# RemoteR2_0.net
KiCad netlist of a schematic drawn in EAGLE
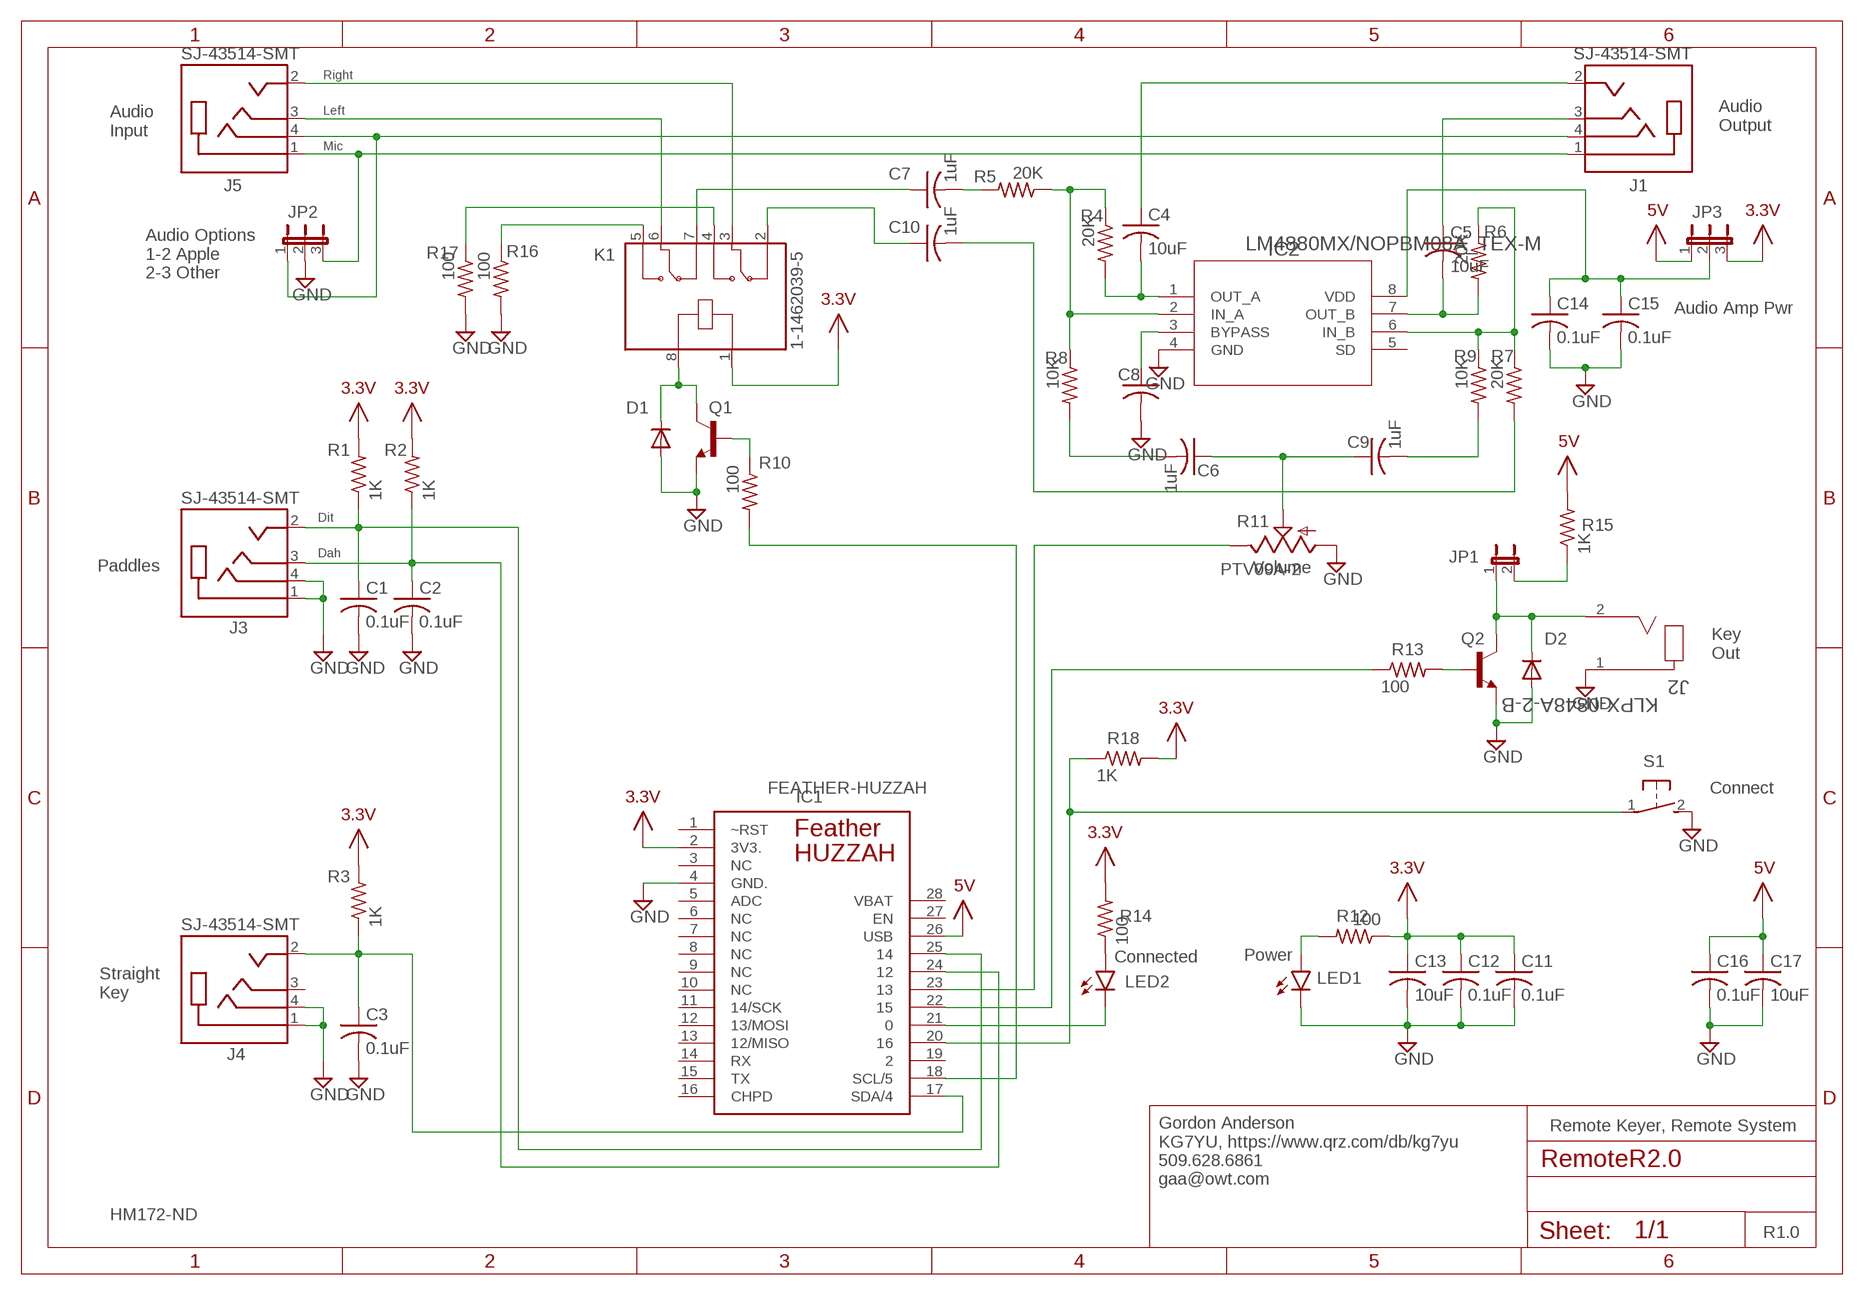
[diagram p0: schematic, sheet 1]

(export (version "E")
  (design (tool "Eeschema 10.0.6"))
  (components
    (comp (ref "C1")
      (value "0.1uF")
      (footprint "eagle-import:C0805")
      (libsource (lib "eagle-import") (part "C-USC0805"))
    )
    (comp (ref "C2")
      (value "0.1uF")
      (footprint "eagle-import:C0805")
      (libsource (lib "eagle-import") (part "C-USC0805"))
    )
    (comp (ref "C3")
      (value "0.1uF")
      (footprint "eagle-import:C0805")
      (libsource (lib "eagle-import") (part "C-USC0805"))
    )
    (comp (ref "C4")
      (value "10uF")
      (footprint "eagle-import:C1206")
      (libsource (lib "eagle-import") (part "C-USC1206"))
    )
    (comp (ref "C5")
      (value "10uF")
      (footprint "eagle-import:C1206")
      (libsource (lib "eagle-import") (part "C-USC1206"))
    )
    (comp (ref "C6")
      (value "1uF")
      (footprint "eagle-import:C0805")
      (libsource (lib "eagle-import") (part "C-USC0805"))
    )
    (comp (ref "C7")
      (value "1uF")
      (footprint "eagle-import:C0805")
      (libsource (lib "eagle-import") (part "C-USC0805"))
    )
    (comp (ref "C8")
      (value "C-USC0805")
      (footprint "eagle-import:C0805")
      (libsource (lib "eagle-import") (part "C-USC0805"))
    )
    (comp (ref "C9")
      (value "1uF")
      (footprint "eagle-import:C0805")
      (libsource (lib "eagle-import") (part "C-USC0805"))
    )
    (comp (ref "C10")
      (value "1uF")
      (footprint "eagle-import:C0805")
      (libsource (lib "eagle-import") (part "C-USC0805"))
    )
    (comp (ref "C11")
      (value "0.1uF")
      (footprint "eagle-import:C0805")
      (libsource (lib "eagle-import") (part "C-USC0805"))
    )
    (comp (ref "C12")
      (value "0.1uF")
      (footprint "eagle-import:C0805")
      (libsource (lib "eagle-import") (part "C-USC0805"))
    )
    (comp (ref "C13")
      (value "10uF")
      (footprint "eagle-import:C0805")
      (libsource (lib "eagle-import") (part "C-USC0805"))
    )
    (comp (ref "C14")
      (value "0.1uF")
      (footprint "eagle-import:C0805")
      (libsource (lib "eagle-import") (part "C-USC0805"))
    )
    (comp (ref "C15")
      (value "0.1uF")
      (footprint "eagle-import:C0805")
      (libsource (lib "eagle-import") (part "C-USC0805"))
    )
    (comp (ref "C16")
      (value "0.1uF")
      (footprint "eagle-import:C0805")
      (libsource (lib "eagle-import") (part "C-USC0805"))
    )
    (comp (ref "C17")
      (value "10uF")
      (footprint "eagle-import:C0805")
      (libsource (lib "eagle-import") (part "C-USC0805"))
    )
    (comp (ref "D1")
      (value "DIODE-SOD323-R")
      (footprint "eagle-import:SOD323-R")
      (libsource (lib "eagle-import") (part "DIODE-SOD323-R"))
    )
    (comp (ref "D2")
      (value "DIODE-SOD323-R")
      (footprint "eagle-import:SOD323-R")
      (libsource (lib "eagle-import") (part "DIODE-SOD323-R"))
    )
    (comp (ref "IC1")
      (value "FEATHER-HUZZAH")
      (footprint "eagle-import:FEATHER-HUZZAH")
      (libsource (lib "eagle-import") (part "FEATHER-HUZZAH"))
    )
    (comp (ref "IC2")
      (value "LM4880MX/NOPBM08A_TEX-M")
      (footprint "eagle-import:M08A_TEX-M")
      (fields
        (field (name "MANUFACTURER_PART_NUMBER") "LM4880MX/NOPB")
        (field (name "COPYRIGHT") "Copyright (C) 2021 Ultra Librarian. All rights reserved.")
      )
      (libsource (lib "eagle-import") (part "LM4880MX/NOPBM08A_TEX-M"))
    )
    (comp (ref "J1")
      (value "SJ-43514-SMT")
      (footprint "eagle-import:CUI_SJ-43514-SMT")
      (fields (field (name "MF") "CUI Devices") (field (name "MP") "SJ-43514-SMT-TR"))
      (libsource (lib "eagle-import") (part "SJ-43514-SMT"))
    )
    (comp (ref "J2")
      (value "KLPX-0848A-2-B")
      (footprint "eagle-import:KLPX-0848A-2-B_KYC")
      (fields (field (name "COPYRIGHT") "Copyright (C) 2021 Ultra Librarian. All rights reserved."))
      (libsource (lib "eagle-import") (part "KLPX-0848A-2-B"))
    )
    (comp (ref "J3")
      (value "SJ-43514-SMT")
      (footprint "eagle-import:CUI_SJ-43514-SMT")
      (fields (field (name "MF") "CUI Devices") (field (name "MP") "SJ-43514-SMT-TR"))
      (libsource (lib "eagle-import") (part "SJ-43514-SMT"))
    )
    (comp (ref "J4")
      (value "SJ-43514-SMT")
      (footprint "eagle-import:CUI_SJ-43514-SMT")
      (fields (field (name "MF") "CUI Devices") (field (name "MP") "SJ-43514-SMT-TR"))
      (libsource (lib "eagle-import") (part "SJ-43514-SMT"))
    )
    (comp (ref "J5")
      (value "SJ-43514-SMT")
      (footprint "eagle-import:CUI_SJ-43514-SMT")
      (fields (field (name "MF") "CUI Devices") (field (name "MP") "SJ-43514-SMT-TR"))
      (libsource (lib "eagle-import") (part "SJ-43514-SMT"))
    )
    (comp (ref "JP1")
      (value "JP1E")
      (footprint "eagle-import:JP1")
      (libsource (lib "eagle-import") (part "JP1E"))
    )
    (comp (ref "JP2")
      (value "JP2E")
      (footprint "eagle-import:JP2")
      (libsource (lib "eagle-import") (part "JP2E"))
    )
    (comp (ref "JP3")
      (value "JP2E")
      (footprint "eagle-import:JP2")
      (libsource (lib "eagle-import") (part "JP2E"))
    )
    (comp (ref "K1")
      (value "1-1462039-5")
      (footprint "eagle-import:RELAY_1-1462039-5")
      (fields (field (name "DIGI-KEY_PART_NUMBER") "PB1167-ND") (field (name "MF") "TE Connectivity"))
      (libsource (lib "eagle-import") (part "1-1462039-5"))
    )
    (comp (ref "LED1")
      (value "LED5MM")
      (footprint "eagle-import:LED5MM")
      (libsource (lib "eagle-import") (part "LED5MM"))
    )
    (comp (ref "LED2")
      (value "LED5MM")
      (footprint "eagle-import:LED5MM")
      (libsource (lib "eagle-import") (part "LED5MM"))
    )
    (comp (ref "Q1")
      (value "MMBT2369LT1-NPN-SOT23-BEC")
      (footprint "eagle-import:SOT23-BEC")
      (libsource (lib "eagle-import") (part "-NPN-SOT23-BECMMBT2369LT1"))
    )
    (comp (ref "Q2")
      (value "MMBT2369LT1-NPN-SOT23-BEC")
      (footprint "eagle-import:SOT23-BEC")
      (libsource (lib "eagle-import") (part "-NPN-SOT23-BECMMBT2369LT1"))
    )
    (comp (ref "R1")
      (value "1K")
      (footprint "eagle-import:R0805")
      (libsource (lib "eagle-import") (part "R-US_R0805"))
    )
    (comp (ref "R2")
      (value "1K")
      (footprint "eagle-import:R0805")
      (libsource (lib "eagle-import") (part "R-US_R0805"))
    )
    (comp (ref "R3")
      (value "1K")
      (footprint "eagle-import:R0805")
      (libsource (lib "eagle-import") (part "R-US_R0805"))
    )
    (comp (ref "R4")
      (value "20K")
      (footprint "eagle-import:R0805")
      (libsource (lib "eagle-import") (part "R-US_R0805"))
    )
    (comp (ref "R5")
      (value "20K")
      (footprint "eagle-import:R0805")
      (libsource (lib "eagle-import") (part "R-US_R0805"))
    )
    (comp (ref "R6")
      (value "20K")
      (footprint "eagle-import:R0805")
      (libsource (lib "eagle-import") (part "R-US_R0805"))
    )
    (comp (ref "R7")
      (value "20K")
      (footprint "eagle-import:R0805")
      (libsource (lib "eagle-import") (part "R-US_R0805"))
    )
    (comp (ref "R8")
      (value "10K")
      (footprint "eagle-import:R0805")
      (libsource (lib "eagle-import") (part "R-US_R0805"))
    )
    (comp (ref "R9")
      (value "10K")
      (footprint "eagle-import:R0805")
      (libsource (lib "eagle-import") (part "R-US_R0805"))
    )
    (comp (ref "R10")
      (value "100")
      (footprint "eagle-import:R0805")
      (libsource (lib "eagle-import") (part "R-US_R0805"))
    )
    (comp (ref "R11")
      (value "PTV09A-2")
      (footprint "eagle-import:PTV09A-2")
      (libsource (lib "eagle-import") (part "PTV09A-2"))
    )
    (comp (ref "R12")
      (value "100")
      (footprint "eagle-import:R0805")
      (libsource (lib "eagle-import") (part "R-US_R0805"))
    )
    (comp (ref "R13")
      (value "100")
      (footprint "eagle-import:R0805")
      (libsource (lib "eagle-import") (part "R-US_R0805"))
    )
    (comp (ref "R14")
      (value "100")
      (footprint "eagle-import:R0805")
      (libsource (lib "eagle-import") (part "R-US_R0805"))
    )
    (comp (ref "R15")
      (value "1K")
      (footprint "eagle-import:R0805")
      (libsource (lib "eagle-import") (part "R-US_R0805"))
    )
    (comp (ref "R16")
      (value "100")
      (footprint "eagle-import:R1206")
      (libsource (lib "eagle-import") (part "R-US_R1206"))
    )
    (comp (ref "R17")
      (value "100")
      (footprint "eagle-import:R1206")
      (libsource (lib "eagle-import") (part "R-US_R1206"))
    )
    (comp (ref "R18")
      (value "1K")
      (footprint "eagle-import:R0805")
      (libsource (lib "eagle-import") (part "R-US_R0805"))
    )
    (comp (ref "S1")
      (value "31-XX")
      (footprint "eagle-import:B3F-31XX")
      (fields (field (name "MPN") "B3F-3100"))
      (libsource (lib "eagle-import") (part "31-XX"))
    )
  )
  (nets
    (net (code "1") (name "/CHPD") (class "Default")
      (node (ref "IC1") (pin "16") (pinfunction "CHPD_16") (pintype "power_in"))
    )
    (net (code "2") (name "/VBAT") (class "Default")
      (node (ref "IC1") (pin "28") (pinfunction "VBAT_28") (pintype "power_in"))
    )
    (net (code "3") (name "3.3V") (class "Default")
      (node (ref "C11") (pin "1") (pinfunction "1_1") (pintype "passive"))
      (node (ref "C12") (pin "1") (pinfunction "1_1") (pintype "passive"))
      (node (ref "C13") (pin "1") (pinfunction "1_1") (pintype "passive"))
      (node (ref "IC1") (pin "2") (pinfunction "3V3._2") (pintype "power_in"))
      (node (ref "JP3") (pin "3") (pinfunction "3_3") (pintype "passive"))
      (node (ref "K1") (pin "1") (pinfunction "1_1") (pintype "passive"))
      (node (ref "R1") (pin "2") (pinfunction "2_2") (pintype "passive"))
      (node (ref "R12") (pin "1") (pinfunction "1_1") (pintype "passive"))
      (node (ref "R14") (pin "2") (pinfunction "2_2") (pintype "passive"))
      (node (ref "R18") (pin "2") (pinfunction "2_2") (pintype "passive"))
      (node (ref "R2") (pin "2") (pinfunction "2_2") (pintype "passive"))
      (node (ref "R3") (pin "2") (pinfunction "2_2") (pintype "passive"))
    )
    (net (code "4") (name "5V") (class "Default")
      (node (ref "C16") (pin "1") (pinfunction "1_1") (pintype "passive"))
      (node (ref "C17") (pin "1") (pinfunction "1_1") (pintype "passive"))
      (node (ref "IC1") (pin "26") (pinfunction "USB_26") (pintype "power_in"))
      (node (ref "JP3") (pin "1") (pinfunction "1_1") (pintype "passive"))
      (node (ref "R15") (pin "2") (pinfunction "2_2") (pintype "passive"))
    )
    (net (code "5") (name "GND") (class "Default")
      (node (ref "C1") (pin "2") (pinfunction "2_2") (pintype "passive"))
      (node (ref "C11") (pin "2") (pinfunction "2_2") (pintype "passive"))
      (node (ref "C12") (pin "2") (pinfunction "2_2") (pintype "passive"))
      (node (ref "C13") (pin "2") (pinfunction "2_2") (pintype "passive"))
      (node (ref "C14") (pin "2") (pinfunction "2_2") (pintype "passive"))
      (node (ref "C15") (pin "2") (pinfunction "2_2") (pintype "passive"))
      (node (ref "C16") (pin "2") (pinfunction "2_2") (pintype "passive"))
      (node (ref "C17") (pin "2") (pinfunction "2_2") (pintype "passive"))
      (node (ref "C2") (pin "2") (pinfunction "2_2") (pintype "passive"))
      (node (ref "C3") (pin "2") (pinfunction "2_2") (pintype "passive"))
      (node (ref "C8") (pin "2") (pinfunction "2_2") (pintype "passive"))
      (node (ref "D1") (pin "A") (pinfunction "A_A") (pintype "passive"))
      (node (ref "D2") (pin "A") (pinfunction "A_A") (pintype "passive"))
      (node (ref "IC1") (pin "4") (pinfunction "GND._4") (pintype "power_in"))
      (node (ref "IC2") (pin "4") (pinfunction "GND_4") (pintype "power_in"))
      (node (ref "J2") (pin "1") (pinfunction "1_1") (pintype "passive"))
      (node (ref "J3") (pin "1") (pinfunction "SLEEVE_1") (pintype "passive"))
      (node (ref "J3") (pin "4") (pinfunction "RING2_4") (pintype "passive"))
      (node (ref "J4") (pin "1") (pinfunction "SLEEVE_1") (pintype "passive"))
      (node (ref "J4") (pin "4") (pinfunction "RING2_4") (pintype "passive"))
      (node (ref "JP2") (pin "2") (pinfunction "2_2") (pintype "passive"))
      (node (ref "LED1") (pin "K") (pinfunction "C_K") (pintype "passive"))
      (node (ref "Q1") (pin "E") (pinfunction "E_E") (pintype "passive"))
      (node (ref "Q2") (pin "E") (pinfunction "E_E") (pintype "passive"))
      (node (ref "R11") (pin "1") (pinfunction "A_1") (pintype "passive"))
      (node (ref "R16") (pin "2") (pinfunction "2_2") (pintype "passive"))
      (node (ref "R17") (pin "2") (pinfunction "2_2") (pintype "passive"))
      (node (ref "S1") (pin "2") (pinfunction "S_2") (pintype "passive"))
    )
    (net (code "6") (name "Net-(C6-Pad2)") (class "Default")
      (node (ref "C6") (pin "2") (pinfunction "2_2") (pintype "passive"))
      (node (ref "R8") (pin "2") (pinfunction "2_2") (pintype "passive"))
    )
    (net (code "7") (name "Net-(C7-Pad1)") (class "Default")
      (node (ref "C7") (pin "1") (pinfunction "1_1") (pintype "passive"))
      (node (ref "K1") (pin "7") (pinfunction "7_7") (pintype "passive"))
    )
    (net (code "8") (name "Net-(C7-Pad2)") (class "Default")
      (node (ref "C7") (pin "2") (pinfunction "2_2") (pintype "passive"))
      (node (ref "R5") (pin "2") (pinfunction "2_2") (pintype "passive"))
    )
    (net (code "9") (name "Net-(C9-Pad2)") (class "Default")
      (node (ref "C9") (pin "2") (pinfunction "2_2") (pintype "passive"))
      (node (ref "R9") (pin "2") (pinfunction "2_2") (pintype "passive"))
    )
    (net (code "10") (name "Net-(C10-Pad1)") (class "Default")
      (node (ref "C10") (pin "1") (pinfunction "1_1") (pintype "passive"))
      (node (ref "K1") (pin "2") (pinfunction "2_2") (pintype "passive"))
    )
    (net (code "11") (name "Net-(C10-Pad2)") (class "Default")
      (node (ref "C10") (pin "2") (pinfunction "2_2") (pintype "passive"))
      (node (ref "R7") (pin "2") (pinfunction "2_2") (pintype "passive"))
    )
    (net (code "12") (name "Net-(D1-PadC)") (class "Default")
      (node (ref "D1") (pin "C") (pinfunction "C_C") (pintype "passive"))
      (node (ref "K1") (pin "8") (pinfunction "8_8") (pintype "passive"))
      (node (ref "Q1") (pin "C") (pinfunction "C_C") (pintype "passive"))
    )
    (net (code "13") (name "Net-(D2-PadC)") (class "Default")
      (node (ref "D2") (pin "C") (pinfunction "C_C") (pintype "passive"))
      (node (ref "J2") (pin "2") (pinfunction "2_2") (pintype "passive"))
      (node (ref "JP1") (pin "1") (pinfunction "1_1") (pintype "passive"))
      (node (ref "Q2") (pin "C") (pinfunction "C_C") (pintype "passive"))
    )
    (net (code "14") (name "Net-(IC1-0)") (class "Default")
      (node (ref "IC1") (pin "21") (pinfunction "0_21") (pintype "bidirectional"))
      (node (ref "LED2") (pin "K") (pinfunction "C_K") (pintype "passive"))
    )
    (net (code "15") (name "Net-(IC1-12)") (class "Default")
      (node (ref "C2") (pin "1") (pinfunction "1_1") (pintype "passive"))
      (node (ref "IC1") (pin "24") (pinfunction "12_24") (pintype "bidirectional"))
      (node (ref "J3") (pin "3") (pinfunction "RING1_3") (pintype "passive"))
      (node (ref "R2") (pin "1") (pinfunction "1_1") (pintype "passive"))
    )
    (net (code "16") (name "Net-(IC1-13)") (class "Default")
      (node (ref "IC1") (pin "23") (pinfunction "13_23") (pintype "bidirectional"))
      (node (ref "R11") (pin "3") (pinfunction "E_3") (pintype "passive"))
    )
    (net (code "17") (name "Net-(IC1-14)") (class "Default")
      (node (ref "C1") (pin "1") (pinfunction "1_1") (pintype "passive"))
      (node (ref "IC1") (pin "25") (pinfunction "14_25") (pintype "bidirectional"))
      (node (ref "J3") (pin "2") (pinfunction "TIP_2") (pintype "passive"))
      (node (ref "R1") (pin "1") (pinfunction "1_1") (pintype "passive"))
    )
    (net (code "18") (name "Net-(IC1-15)") (class "Default")
      (node (ref "IC1") (pin "22") (pinfunction "15_22") (pintype "bidirectional"))
      (node (ref "R13") (pin "1") (pinfunction "1_1") (pintype "passive"))
    )
    (net (code "19") (name "Net-(IC1-16)") (class "Default")
      (node (ref "IC1") (pin "20") (pinfunction "16_20") (pintype "bidirectional"))
      (node (ref "R18") (pin "1") (pinfunction "1_1") (pintype "passive"))
      (node (ref "S1") (pin "1") (pinfunction "P_1") (pintype "passive"))
    )
    (net (code "20") (name "Net-(IC1-SCL{slash}5)") (class "Default")
      (node (ref "IC1") (pin "18") (pinfunction "SCL/5_18") (pintype "bidirectional"))
      (node (ref "R10") (pin "2") (pinfunction "2_2") (pintype "passive"))
    )
    (net (code "21") (name "Net-(IC1-SDA{slash}4)") (class "Default")
      (node (ref "C3") (pin "1") (pinfunction "1_1") (pintype "passive"))
      (node (ref "IC1") (pin "17") (pinfunction "SDA/4_17") (pintype "bidirectional"))
      (node (ref "J4") (pin "2") (pinfunction "TIP_2") (pintype "passive"))
      (node (ref "R3") (pin "1") (pinfunction "1_1") (pintype "passive"))
    )
    (net (code "22") (name "Net-(IC2-BYPASS)") (class "Default")
      (node (ref "C8") (pin "1") (pinfunction "1_1") (pintype "passive"))
      (node (ref "IC2") (pin "3") (pinfunction "BYPASS_3") (pintype "passive"))
    )
    (net (code "23") (name "Net-(IC2-IN_A)") (class "Default")
      (node (ref "IC2") (pin "2") (pinfunction "IN_A_2") (pintype "input"))
      (node (ref "R4") (pin "1") (pinfunction "1_1") (pintype "passive"))
      (node (ref "R5") (pin "1") (pinfunction "1_1") (pintype "passive"))
      (node (ref "R8") (pin "1") (pinfunction "1_1") (pintype "passive"))
    )
    (net (code "24") (name "Net-(IC2-IN_B)") (class "Default")
      (node (ref "IC2") (pin "6") (pinfunction "IN_B_6") (pintype "input"))
      (node (ref "R6") (pin "1") (pinfunction "1_1") (pintype "passive"))
      (node (ref "R7") (pin "1") (pinfunction "1_1") (pintype "passive"))
      (node (ref "R9") (pin "1") (pinfunction "1_1") (pintype "passive"))
    )
    (net (code "25") (name "Net-(IC2-OUT_A)") (class "Default")
      (node (ref "C4") (pin "2") (pinfunction "2_2") (pintype "passive"))
      (node (ref "IC2") (pin "1") (pinfunction "OUT_A_1") (pintype "output"))
      (node (ref "R4") (pin "2") (pinfunction "2_2") (pintype "passive"))
    )
    (net (code "26") (name "Net-(IC2-OUT_B)") (class "Default")
      (node (ref "C5") (pin "2") (pinfunction "2_2") (pintype "passive"))
      (node (ref "IC2") (pin "7") (pinfunction "OUT_B_7") (pintype "output"))
      (node (ref "R6") (pin "2") (pinfunction "2_2") (pintype "passive"))
    )
    (net (code "27") (name "Net-(IC2-VDD)") (class "Default")
      (node (ref "C14") (pin "1") (pinfunction "1_1") (pintype "passive"))
      (node (ref "C15") (pin "1") (pinfunction "1_1") (pintype "passive"))
      (node (ref "IC2") (pin "8") (pinfunction "VDD_8") (pintype "power_in"))
      (node (ref "JP3") (pin "2") (pinfunction "2_2") (pintype "passive"))
    )
    (net (code "28") (name "Net-(J1-RING1)") (class "Default")
      (node (ref "C5") (pin "1") (pinfunction "1_1") (pintype "passive"))
      (node (ref "J1") (pin "3") (pinfunction "RING1_3") (pintype "passive"))
    )
    (net (code "29") (name "Net-(J1-RING2)") (class "Default")
      (node (ref "J1") (pin "4") (pinfunction "RING2_4") (pintype "passive"))
      (node (ref "J5") (pin "4") (pinfunction "RING2_4") (pintype "passive"))
      (node (ref "JP2") (pin "1") (pinfunction "1_1") (pintype "passive"))
    )
    (net (code "30") (name "Net-(J1-SLEEVE)") (class "Default")
      (node (ref "J1") (pin "1") (pinfunction "SLEEVE_1") (pintype "passive"))
      (node (ref "J5") (pin "1") (pinfunction "SLEEVE_1") (pintype "passive"))
      (node (ref "JP2") (pin "3") (pinfunction "3_3") (pintype "passive"))
    )
    (net (code "31") (name "Net-(J1-TIP)") (class "Default")
      (node (ref "C4") (pin "1") (pinfunction "1_1") (pintype "passive"))
      (node (ref "J1") (pin "2") (pinfunction "TIP_2") (pintype "passive"))
    )
    (net (code "32") (name "Net-(J5-RING1)") (class "Default")
      (node (ref "J5") (pin "3") (pinfunction "RING1_3") (pintype "passive"))
      (node (ref "K1") (pin "6") (pinfunction "6_6") (pintype "passive"))
    )
    (net (code "33") (name "Net-(J5-TIP)") (class "Default")
      (node (ref "J5") (pin "2") (pinfunction "TIP_2") (pintype "passive"))
      (node (ref "K1") (pin "3") (pinfunction "3_3") (pintype "passive"))
    )
    (net (code "34") (name "Net-(JP1-Pad2)") (class "Default")
      (node (ref "JP1") (pin "2") (pinfunction "2_2") (pintype "passive"))
      (node (ref "R15") (pin "1") (pinfunction "1_1") (pintype "passive"))
    )
    (net (code "35") (name "Net-(K1-Pad4)") (class "Default")
      (node (ref "K1") (pin "4") (pinfunction "4_4") (pintype "passive"))
      (node (ref "R17") (pin "1") (pinfunction "1_1") (pintype "passive"))
    )
    (net (code "36") (name "Net-(K1-Pad5)") (class "Default")
      (node (ref "K1") (pin "5") (pinfunction "5_5") (pintype "passive"))
      (node (ref "R16") (pin "1") (pinfunction "1_1") (pintype "passive"))
    )
    (net (code "37") (name "Net-(LED1-PadA)") (class "Default")
      (node (ref "LED1") (pin "A") (pinfunction "A_A") (pintype "passive"))
      (node (ref "R12") (pin "2") (pinfunction "2_2") (pintype "passive"))
    )
    (net (code "38") (name "Net-(LED2-PadA)") (class "Default")
      (node (ref "LED2") (pin "A") (pinfunction "A_A") (pintype "passive"))
      (node (ref "R14") (pin "1") (pinfunction "1_1") (pintype "passive"))
    )
    (net (code "39") (name "Net-(Q1-PadB)") (class "Default")
      (node (ref "Q1") (pin "B") (pinfunction "B_B") (pintype "passive"))
      (node (ref "R10") (pin "1") (pinfunction "1_1") (pintype "passive"))
    )
    (net (code "40") (name "Net-(Q2-PadB)") (class "Default")
      (node (ref "Q2") (pin "B") (pinfunction "B_B") (pintype "passive"))
      (node (ref "R13") (pin "2") (pinfunction "2_2") (pintype "passive"))
    )
    (net (code "41") (name "Net-(R11-S)") (class "Default")
      (node (ref "C6") (pin "1") (pinfunction "1_1") (pintype "passive"))
      (node (ref "C9") (pin "1") (pinfunction "1_1") (pintype "passive"))
      (node (ref "R11") (pin "2") (pinfunction "S_2") (pintype "passive"))
    )
    (net (code "42") (name "unconnected-(IC1-2-Pad19)") (class "Default")
      (node (ref "IC1") (pin "19") (pinfunction "2_19") (pintype "bidirectional"))
    )
    (net (code "43") (name "unconnected-(IC1-12{slash}MISO-Pad13)") (class "Default")
      (node (ref "IC1") (pin "13") (pinfunction "12/MISO_13") (pintype "bidirectional"))
    )
    (net (code "44") (name "unconnected-(IC1-13{slash}MOSI-Pad12)") (class "Default")
      (node (ref "IC1") (pin "12") (pinfunction "13/MOSI_12") (pintype "bidirectional"))
    )
    (net (code "45") (name "unconnected-(IC1-14{slash}SCK-Pad11)") (class "Default")
      (node (ref "IC1") (pin "11") (pinfunction "14/SCK_11") (pintype "bidirectional"))
    )
    (net (code "46") (name "unconnected-(IC1-ADC-Pad5)") (class "Default")
      (node (ref "IC1") (pin "5") (pinfunction "ADC_5") (pintype "bidirectional"))
    )
    (net (code "47") (name "unconnected-(IC1-EN-Pad27)") (class "Default")
      (node (ref "IC1") (pin "27") (pinfunction "EN_27") (pintype "input"))
    )
    (net (code "48") (name "unconnected-(IC1-NC-Pad3)") (class "Default")
      (node (ref "IC1") (pin "3") (pinfunction "NC_3") (pintype "input"))
    )
    (net (code "49") (name "unconnected-(IC1-NC-Pad6)") (class "Default")
      (node (ref "IC1") (pin "6") (pinfunction "NC_6") (pintype "bidirectional"))
    )
    (net (code "50") (name "unconnected-(IC1-NC-Pad7)") (class "Default")
      (node (ref "IC1") (pin "7") (pinfunction "NC_7") (pintype "bidirectional"))
    )
    (net (code "51") (name "unconnected-(IC1-NC-Pad8)") (class "Default")
      (node (ref "IC1") (pin "8") (pinfunction "NC_8") (pintype "bidirectional"))
    )
    (net (code "52") (name "unconnected-(IC1-NC-Pad9)") (class "Default")
      (node (ref "IC1") (pin "9") (pinfunction "NC_9") (pintype "bidirectional"))
    )
    (net (code "53") (name "unconnected-(IC1-NC-Pad10)") (class "Default")
      (node (ref "IC1") (pin "10") (pinfunction "NC_10") (pintype "bidirectional"))
    )
    (net (code "54") (name "unconnected-(IC1-RX-Pad14)") (class "Default")
      (node (ref "IC1") (pin "14") (pinfunction "RX_14") (pintype "bidirectional"))
    )
    (net (code "55") (name "unconnected-(IC1-TX-Pad15)") (class "Default")
      (node (ref "IC1") (pin "15") (pinfunction "TX_15") (pintype "bidirectional"))
    )
    (net (code "56") (name "unconnected-(IC1-~{RST}-Pad1)") (class "Default")
      (node (ref "IC1") (pin "1") (pinfunction "~{RST}_1") (pintype "input"))
    )
    (net (code "57") (name "unconnected-(IC2-SD-Pad5)") (class "Default")
      (node (ref "IC2") (pin "5") (pinfunction "SD_5") (pintype "input"))
    )
    (net (code "58") (name "unconnected-(J4-RING1-Pad3)") (class "Default")
      (node (ref "J4") (pin "3") (pinfunction "RING1_3") (pintype "passive"))
    )
  )
)
